# mainboard.net
KiCad netlist of a schematic drawn in EAGLE
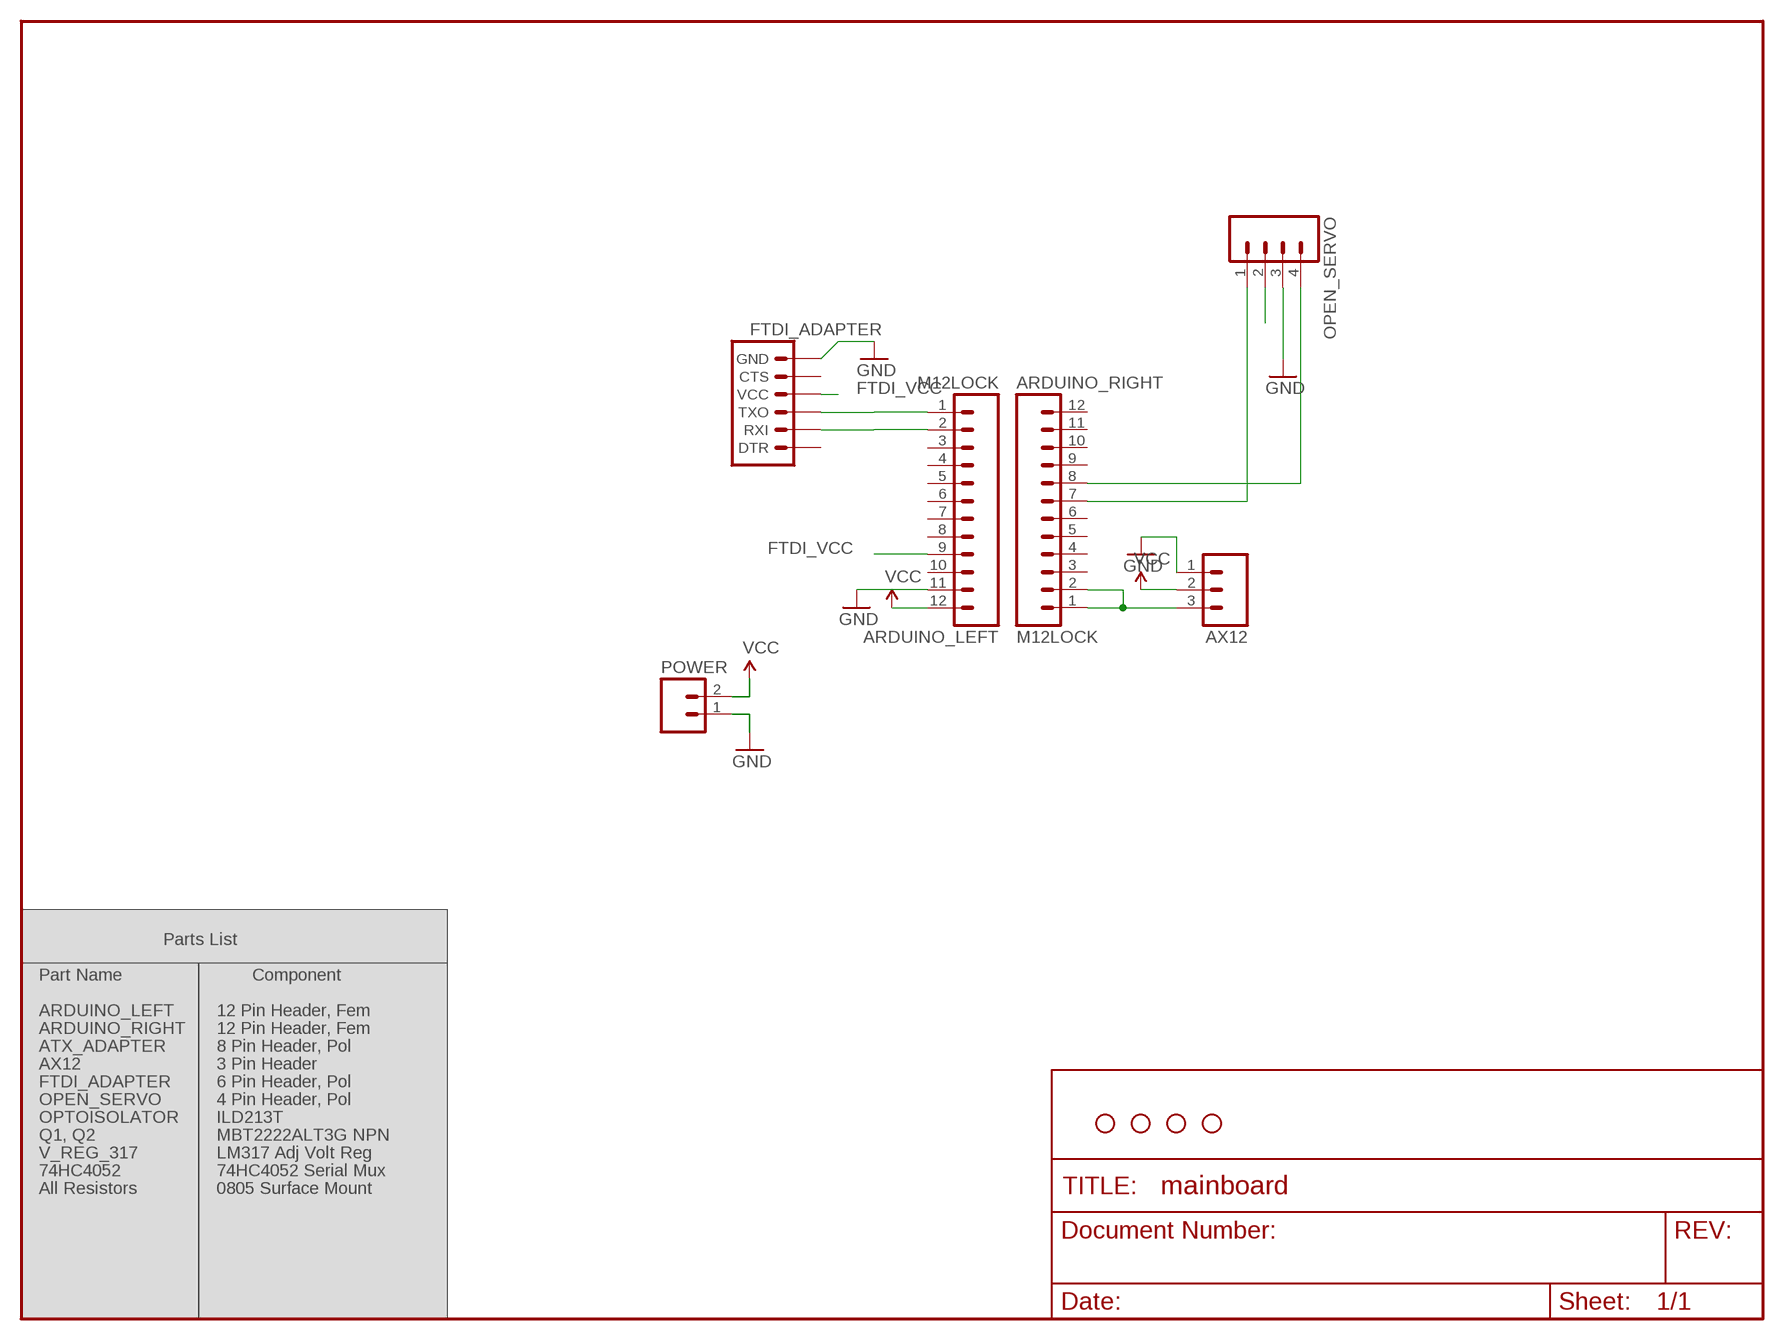
[diagram p0: schematic, sheet 1]

(export (version "E")
  (design (tool "Eeschema 10.0.6"))
  (components
    (comp (ref "ARDUINO_LEFT")
      (value "M12LOCK")
      (footprint "eagle-import:1X12_LOCK")
      (libsource (lib "eagle-import") (part "M12LOCK"))
    )
    (comp (ref "ARDUINO_RIGHT")
      (value "M12LOCK")
      (footprint "eagle-import:1X12_LOCK")
      (libsource (lib "eagle-import") (part "M12LOCK"))
    )
    (comp (ref "AX12")
      (value "M03LOCK")
      (footprint "eagle-import:1X03_LOCK")
      (libsource (lib "eagle-import") (part "M03LOCK"))
    )
    (comp (ref "FTDI_ADAPTER")
      (value "ARDUINO_SERIAL_PROGRAMLOCK")
      (footprint "eagle-import:1X06_LOCK")
      (libsource (lib "eagle-import") (part "ARDUINO_SERIAL_PROGRAMLOCK"))
    )
    (comp (ref "JP1")
      (value "STAND-OFF")
      (footprint "eagle-import:STAND-OFF")
      (libsource (lib "eagle-import") (part "STAND-OFF"))
    )
    (comp (ref "JP2")
      (value "STAND-OFF")
      (footprint "eagle-import:STAND-OFF")
      (libsource (lib "eagle-import") (part "STAND-OFF"))
    )
    (comp (ref "JP3")
      (value "STAND-OFF")
      (footprint "eagle-import:STAND-OFF")
      (libsource (lib "eagle-import") (part "STAND-OFF"))
    )
    (comp (ref "JP4")
      (value "STAND-OFF")
      (footprint "eagle-import:STAND-OFF")
      (libsource (lib "eagle-import") (part "STAND-OFF"))
    )
    (comp (ref "OPEN_SERVO")
      (value "M04LOCK")
      (footprint "eagle-import:1X04_LOCK")
      (libsource (lib "eagle-import") (part "M04LOCK"))
    )
    (comp (ref "POWER")
      (value "M023.5MM")
      (footprint "eagle-import:SCREWTERMINAL-3.5MM-2")
      (libsource (lib "eagle-import") (part "M023.5MM"))
    )
  )
  (nets
    (net (code "1") (name "/FTDI_RX") (class "Default")
      (node (ref "ARDUINO_LEFT") (pin "2") (pinfunction "2_2") (pintype "passive"))
      (node (ref "FTDI_ADAPTER") (pin "2") (pinfunction "RXI_2") (pintype "passive"))
    )
    (net (code "2") (name "/FTDI_TX") (class "Default")
      (node (ref "ARDUINO_LEFT") (pin "1") (pinfunction "1_1") (pintype "passive"))
      (node (ref "FTDI_ADAPTER") (pin "3") (pinfunction "TXO_3") (pintype "passive"))
    )
    (net (code "3") (name "/FTDI_VCC") (class "Default")
      (node (ref "ARDUINO_LEFT") (pin "9") (pinfunction "9_9") (pintype "passive"))
      (node (ref "FTDI_ADAPTER") (pin "4") (pinfunction "VCC_4") (pintype "passive"))
    )
    (net (code "4") (name "GND") (class "Default")
      (node (ref "ARDUINO_LEFT") (pin "11") (pinfunction "11_11") (pintype "passive"))
      (node (ref "AX12") (pin "1") (pinfunction "1_1") (pintype "passive"))
      (node (ref "FTDI_ADAPTER") (pin "6") (pinfunction "GND_6") (pintype "passive"))
      (node (ref "OPEN_SERVO") (pin "3") (pinfunction "3_3") (pintype "passive"))
      (node (ref "POWER") (pin "1") (pinfunction "1_1") (pintype "passive"))
    )
    (net (code "5") (name "Net-(ARDUINO_RIGHT-Pad1)") (class "Default")
      (node (ref "ARDUINO_RIGHT") (pin "1") (pinfunction "1_1") (pintype "passive"))
      (node (ref "ARDUINO_RIGHT") (pin "2") (pinfunction "2_2") (pintype "passive"))
      (node (ref "AX12") (pin "3") (pinfunction "3_3") (pintype "passive"))
    )
    (net (code "6") (name "Net-(ARDUINO_RIGHT-Pad7)") (class "Default")
      (node (ref "ARDUINO_RIGHT") (pin "7") (pinfunction "7_7") (pintype "passive"))
      (node (ref "OPEN_SERVO") (pin "1") (pinfunction "1_1") (pintype "passive"))
    )
    (net (code "7") (name "Net-(ARDUINO_RIGHT-Pad8)") (class "Default")
      (node (ref "ARDUINO_RIGHT") (pin "8") (pinfunction "8_8") (pintype "passive"))
      (node (ref "OPEN_SERVO") (pin "4") (pinfunction "4_4") (pintype "passive"))
    )
    (net (code "8") (name "VCC") (class "Default")
      (node (ref "ARDUINO_LEFT") (pin "12") (pinfunction "12_12") (pintype "passive"))
      (node (ref "AX12") (pin "2") (pinfunction "2_2") (pintype "passive"))
      (node (ref "POWER") (pin "2") (pinfunction "2_2") (pintype "passive"))
    )
    (net (code "9") (name "unconnected-(ARDUINO_LEFT-Pad3)") (class "Default")
      (node (ref "ARDUINO_LEFT") (pin "3") (pinfunction "3_3") (pintype "passive"))
    )
    (net (code "10") (name "unconnected-(ARDUINO_LEFT-Pad4)") (class "Default")
      (node (ref "ARDUINO_LEFT") (pin "4") (pinfunction "4_4") (pintype "passive"))
    )
    (net (code "11") (name "unconnected-(ARDUINO_LEFT-Pad5)") (class "Default")
      (node (ref "ARDUINO_LEFT") (pin "5") (pinfunction "5_5") (pintype "passive"))
    )
    (net (code "12") (name "unconnected-(ARDUINO_LEFT-Pad6)") (class "Default")
      (node (ref "ARDUINO_LEFT") (pin "6") (pinfunction "6_6") (pintype "passive"))
    )
    (net (code "13") (name "unconnected-(ARDUINO_LEFT-Pad7)") (class "Default")
      (node (ref "ARDUINO_LEFT") (pin "7") (pinfunction "7_7") (pintype "passive"))
    )
    (net (code "14") (name "unconnected-(ARDUINO_LEFT-Pad8)") (class "Default")
      (node (ref "ARDUINO_LEFT") (pin "8") (pinfunction "8_8") (pintype "passive"))
    )
    (net (code "15") (name "unconnected-(ARDUINO_LEFT-Pad10)") (class "Default")
      (node (ref "ARDUINO_LEFT") (pin "10") (pinfunction "10_10") (pintype "passive"))
    )
    (net (code "16") (name "unconnected-(ARDUINO_RIGHT-Pad3)") (class "Default")
      (node (ref "ARDUINO_RIGHT") (pin "3") (pinfunction "3_3") (pintype "passive"))
    )
    (net (code "17") (name "unconnected-(ARDUINO_RIGHT-Pad4)") (class "Default")
      (node (ref "ARDUINO_RIGHT") (pin "4") (pinfunction "4_4") (pintype "passive"))
    )
    (net (code "18") (name "unconnected-(ARDUINO_RIGHT-Pad5)") (class "Default")
      (node (ref "ARDUINO_RIGHT") (pin "5") (pinfunction "5_5") (pintype "passive"))
    )
    (net (code "19") (name "unconnected-(ARDUINO_RIGHT-Pad6)") (class "Default")
      (node (ref "ARDUINO_RIGHT") (pin "6") (pinfunction "6_6") (pintype "passive"))
    )
    (net (code "20") (name "unconnected-(ARDUINO_RIGHT-Pad9)") (class "Default")
      (node (ref "ARDUINO_RIGHT") (pin "9") (pinfunction "9_9") (pintype "passive"))
    )
    (net (code "21") (name "unconnected-(ARDUINO_RIGHT-Pad10)") (class "Default")
      (node (ref "ARDUINO_RIGHT") (pin "10") (pinfunction "10_10") (pintype "passive"))
    )
    (net (code "22") (name "unconnected-(ARDUINO_RIGHT-Pad11)") (class "Default")
      (node (ref "ARDUINO_RIGHT") (pin "11") (pinfunction "11_11") (pintype "passive"))
    )
    (net (code "23") (name "unconnected-(ARDUINO_RIGHT-Pad12)") (class "Default")
      (node (ref "ARDUINO_RIGHT") (pin "12") (pinfunction "12_12") (pintype "passive"))
    )
    (net (code "24") (name "unconnected-(FTDI_ADAPTER-CTS-Pad5)") (class "Default")
      (node (ref "FTDI_ADAPTER") (pin "5") (pinfunction "CTS_5") (pintype "passive"))
    )
    (net (code "25") (name "unconnected-(FTDI_ADAPTER-DTR-Pad1)") (class "Default")
      (node (ref "FTDI_ADAPTER") (pin "1") (pinfunction "DTR_1") (pintype "passive"))
    )
    (net (code "26") (name "unconnected-(OPEN_SERVO-Pad2)") (class "Default")
      (node (ref "OPEN_SERVO") (pin "2") (pinfunction "2_2") (pintype "passive"))
    )
  )
)
